# Sheet1.net
KiCad netlist of a schematic drawn in Altium Designer
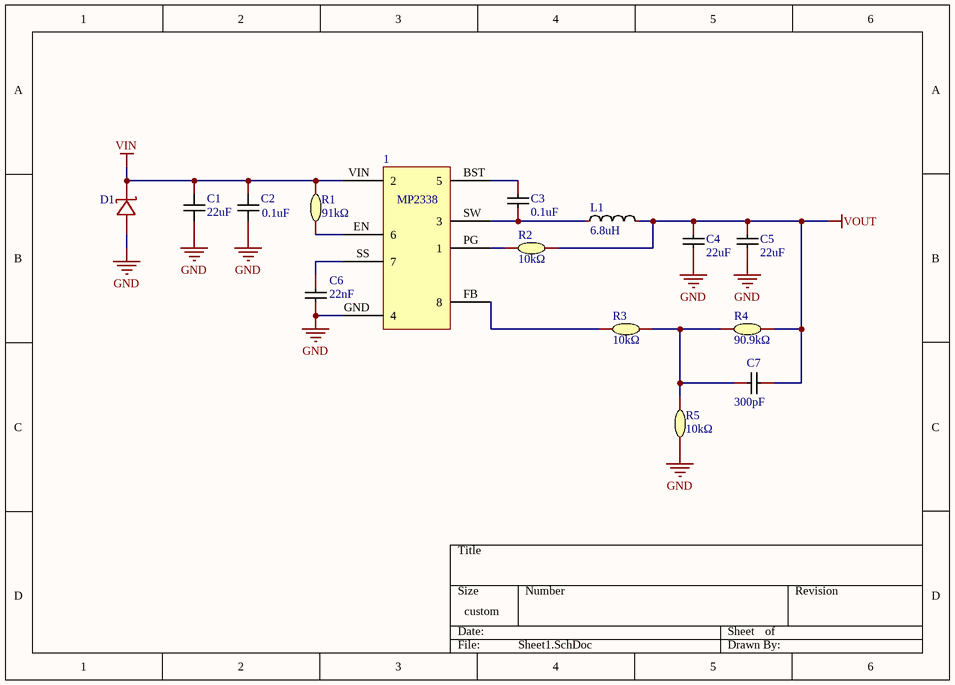
[diagram p0: Sheet1.SchDoc]

(export (version "E")
  (design (tool "Eeschema 10.0.6"))
  (components
    (comp (ref "*") (value "D1") (footprint "PCBComponent_1") (libsource (lib "TVS") (part "Component_1")))
    (comp (ref "1") (value "MP2338") (footprint "PCBComponent_1") (libsource (lib "Schlib1") (part "MP2338")))
    (comp (ref "C1")
      (value "22uF")
      (footprint "C0805")
      (description "容值:22uF;精度:±20%;额定电压:25V;材质(温度系数):X5R;")
      (fields
        (field (name "MANUFACTURER") "SAMSUNG(三星)")
        (field (name "MANUFACTURER PART") "CL21A226MAQNNNE")
        (field (name "NAME") "22uF")
      )
      (libsource (lib "YHT_Y170_SCH") (part "CL21A226MAQNNNE_C45783"))
    )
    (comp (ref "C2")
      (value "0.1uF")
      (footprint "C0805")
      (description "容值:22uF;精度:±20%;额定电压:25V;材质(温度系数):X5R;")
      (fields
        (field (name "MANUFACTURER") "SAMSUNG(三星)")
        (field (name "MANUFACTURER PART") "CL21A226MAQNNNE")
        (field (name "NAME") "0.1uF")
      )
      (libsource (lib "YHT_Y170_SCH") (part "CL21A226MAQNNNE_C45783"))
    )
    (comp (ref "C3")
      (value "0.1uF")
      (footprint "C0603")
      (description "容值:2.2uF;精度:±10%;额定电压:16V;材质(温度系数):X5R;")
      (fields
        (field (name "MANUFACTURER") "SAMSUNG(三星)")
        (field (name "MANUFACTURER PART") "CL10A225KO8NNNC")
        (field (name "NAME") "0.1uF")
      )
      (libsource (lib "YHT_Y170_SCH") (part "CL10A225KO8NNNC"))
    )
    (comp (ref "C4")
      (value "22uF")
      (footprint "C0603")
      (description "容值:2.2uF;精度:±10%;额定电压:16V;材质(温度系数):X5R;")
      (fields
        (field (name "MANUFACTURER") "SAMSUNG(三星)")
        (field (name "MANUFACTURER PART") "CL10A225KO8NNNC")
        (field (name "NAME") "22uF")
      )
      (libsource (lib "YHT_Y170_SCH") (part "CL10A225KO8NNNC"))
    )
    (comp (ref "C5")
      (value "22uF")
      (footprint "C0603")
      (description "容值:2.2uF;精度:±10%;额定电压:16V;材质(温度系数):X5R;")
      (fields
        (field (name "MANUFACTURER") "SAMSUNG(三星)")
        (field (name "MANUFACTURER PART") "CL10A225KO8NNNC")
        (field (name "NAME") "22uF")
      )
      (libsource (lib "YHT_Y170_SCH") (part "CL10A225KO8NNNC"))
    )
    (comp (ref "C6")
      (value "22nF")
      (footprint "C0603")
      (description "容值:2.2uF;精度:±10%;额定电压:16V;材质(温度系数):X5R;")
      (fields
        (field (name "MANUFACTURER") "SAMSUNG(三星)")
        (field (name "MANUFACTURER PART") "CL10A225KO8NNNC")
        (field (name "NAME") "22nF")
      )
      (libsource (lib "YHT_Y170_SCH") (part "CL10A225KO8NNNC"))
    )
    (comp (ref "C7")
      (value "300pF")
      (footprint "C0603")
      (description "容值:2.2uF;精度:±10%;额定电压:16V;材质(温度系数):X5R;")
      (fields
        (field (name "MANUFACTURER") "SAMSUNG(三星)")
        (field (name "MANUFACTURER PART") "CL10A225KO8NNNC")
        (field (name "NAME") "300pF")
      )
      (libsource (lib "YHT_Y170_SCH") (part "CL10A225KO8NNNC"))
    )
    (comp (ref "L1")
      (value "6.8uH")
      (footprint "IND-SMD_L7.0-W6.6")
      (description "电感值:2.2uH;精度:±20%;额定电流:9.5A;直流电阻(DCR):15mΩ;")
      (fields
        (field (name "MANUFACTURER") "Sunlord(顺络)")
        (field (name "MANUFACTURER PART") "MWSA0603S-2R2MT")
        (field (name "NAME") "6.8uH")
      )
      (libsource (lib "YHT_Y170_SCH") (part "MWSA0603S-2R2MT"))
    )
    (comp (ref "R1")
      (value "191kΩ")
      (footprint "R0603")
      (description "电阻类型:厚膜电阻;阻值:10kΩ;精度:±1%;功率:100mW;温度系数:±100ppm/℃;最大工作电压:75V;工作温度范围:-55℃~+155℃;")
      (fields
        (field (name "MANUFACTURER") "UNI-ROYAL(厚声)")
        (field (name "MANUFACTURER PART") "0603WAF1002T5E")
        (field (name "NAME") "191kΩ")
      )
      (libsource (lib "YHT_Y170_SCH") (part "0603WAF1002T5E"))
    )
    (comp (ref "R2")
      (value "10kΩ")
      (footprint "R0603")
      (description "电阻类型:厚膜电阻;阻值:10kΩ;精度:±1%;功率:100mW;温度系数:±100ppm/℃;最大工作电压:75V;工作温度范围:-55℃~+155℃;")
      (fields
        (field (name "MANUFACTURER") "UNI-ROYAL(厚声)")
        (field (name "MANUFACTURER PART") "0603WAF1002T5E")
        (field (name "NAME") "10kΩ")
      )
      (libsource (lib "YHT_Y170_SCH") (part "0603WAF1002T5E"))
    )
    (comp (ref "R3")
      (value "10kΩ")
      (footprint "R0603")
      (description "电阻类型:厚膜电阻;阻值:10kΩ;精度:±1%;功率:100mW;温度系数:±100ppm/℃;最大工作电压:75V;工作温度范围:-55℃~+155℃;")
      (fields
        (field (name "MANUFACTURER") "UNI-ROYAL(厚声)")
        (field (name "MANUFACTURER PART") "0603WAF1002T5E")
        (field (name "NAME") "10kΩ")
      )
      (libsource (lib "YHT_Y170_SCH") (part "0603WAF1002T5E"))
    )
    (comp (ref "R4")
      (value "90.9kΩ")
      (footprint "R0603")
      (description "电阻类型:厚膜电阻;阻值:10kΩ;精度:±1%;功率:100mW;温度系数:±100ppm/℃;最大工作电压:75V;工作温度范围:-55℃~+155℃;")
      (fields
        (field (name "MANUFACTURER") "UNI-ROYAL(厚声)")
        (field (name "MANUFACTURER PART") "0603WAF1002T5E")
        (field (name "NAME") "90.9kΩ")
      )
      (libsource (lib "YHT_Y170_SCH") (part "0603WAF1002T5E"))
    )
    (comp (ref "R5")
      (value "10kΩ")
      (footprint "R0603")
      (description "电阻类型:厚膜电阻;阻值:10kΩ;精度:±1%;功率:100mW;温度系数:±100ppm/℃;最大工作电压:75V;工作温度范围:-55℃~+155℃;")
      (fields
        (field (name "MANUFACTURER") "UNI-ROYAL(厚声)")
        (field (name "MANUFACTURER PART") "0603WAF1002T5E")
        (field (name "NAME") "10kΩ")
      )
      (libsource (lib "YHT_Y170_SCH") (part "0603WAF1002T5E"))
    )
  )
  (nets
    (net (code "1") (name "GND") (class "Default")
      (node (ref "*") (pin "2") (pinfunction "A_2") (pintype "passive"))
      (node (ref "1") (pin "GND") (pinfunction "4_GND") (pintype "passive"))
      (node (ref "C1") (pin "1") (pinfunction "1_1") (pintype "passive"))
      (node (ref "C2") (pin "1") (pinfunction "1_1") (pintype "passive"))
      (node (ref "C4") (pin "1") (pinfunction "1_1") (pintype "passive"))
      (node (ref "C5") (pin "1") (pinfunction "1_1") (pintype "passive"))
      (node (ref "C6") (pin "1") (pinfunction "1_1") (pintype "passive"))
      (node (ref "R5") (pin "1") (pinfunction "1_1") (pintype "passive"))
    )
    (net (code "2") (name "Net-(1-1)") (class "Default")
      (node (ref "1") (pin "PG") (pinfunction "1_PG") (pintype "passive"))
      (node (ref "R2") (pin "1") (pinfunction "1_1") (pintype "passive"))
    )
    (net (code "3") (name "Net-(1-3)") (class "Default")
      (node (ref "1") (pin "SW") (pinfunction "3_SW") (pintype "passive"))
      (node (ref "C3") (pin "1") (pinfunction "1_1") (pintype "passive"))
      (node (ref "L1") (pin "1") (pinfunction "1_1") (pintype "passive"))
    )
    (net (code "4") (name "Net-(1-5)") (class "Default")
      (node (ref "1") (pin "BST") (pinfunction "5_BST") (pintype "passive"))
      (node (ref "C3") (pin "2") (pinfunction "2_2") (pintype "passive"))
    )
    (net (code "5") (name "Net-(1-6)") (class "Default")
      (node (ref "1") (pin "EN") (pinfunction "6_EN") (pintype "passive"))
      (node (ref "R1") (pin "1") (pinfunction "1_1") (pintype "passive"))
    )
    (net (code "6") (name "Net-(1-7)") (class "Default")
      (node (ref "1") (pin "SS") (pinfunction "7_SS") (pintype "passive"))
      (node (ref "C6") (pin "2") (pinfunction "2_2") (pintype "passive"))
    )
    (net (code "7") (name "Net-(1-8)") (class "Default")
      (node (ref "1") (pin "FB") (pinfunction "8_FB") (pintype "passive"))
      (node (ref "R3") (pin "1") (pinfunction "1_1") (pintype "passive"))
    )
    (net (code "8") (name "Net-(C7-Pad1)") (class "Default")
      (node (ref "C7") (pin "1") (pinfunction "1_1") (pintype "passive"))
      (node (ref "R3") (pin "2") (pinfunction "2_2") (pintype "passive"))
      (node (ref "R4") (pin "1") (pinfunction "1_1") (pintype "passive"))
      (node (ref "R5") (pin "2") (pinfunction "2_2") (pintype "passive"))
    )
    (net (code "9") (name "VIN") (class "Default")
      (node (ref "*") (pin "1") (pinfunction "K_1") (pintype "passive"))
      (node (ref "1") (pin "VIN") (pinfunction "2_VIN") (pintype "passive"))
      (node (ref "C1") (pin "2") (pinfunction "2_2") (pintype "passive"))
      (node (ref "C2") (pin "2") (pinfunction "2_2") (pintype "passive"))
      (node (ref "R1") (pin "2") (pinfunction "2_2") (pintype "passive"))
    )
    (net (code "10") (name "VOUT") (class "Default")
      (node (ref "C4") (pin "2") (pinfunction "2_2") (pintype "passive"))
      (node (ref "C5") (pin "2") (pinfunction "2_2") (pintype "passive"))
      (node (ref "C7") (pin "2") (pinfunction "2_2") (pintype "passive"))
      (node (ref "L1") (pin "2") (pinfunction "2_2") (pintype "passive"))
      (node (ref "R2") (pin "2") (pinfunction "2_2") (pintype "passive"))
      (node (ref "R4") (pin "2") (pinfunction "2_2") (pintype "passive"))
    )
  )
)
